# Level_Detector.net
KiCad netlist of a schematic drawn in Altium Designer
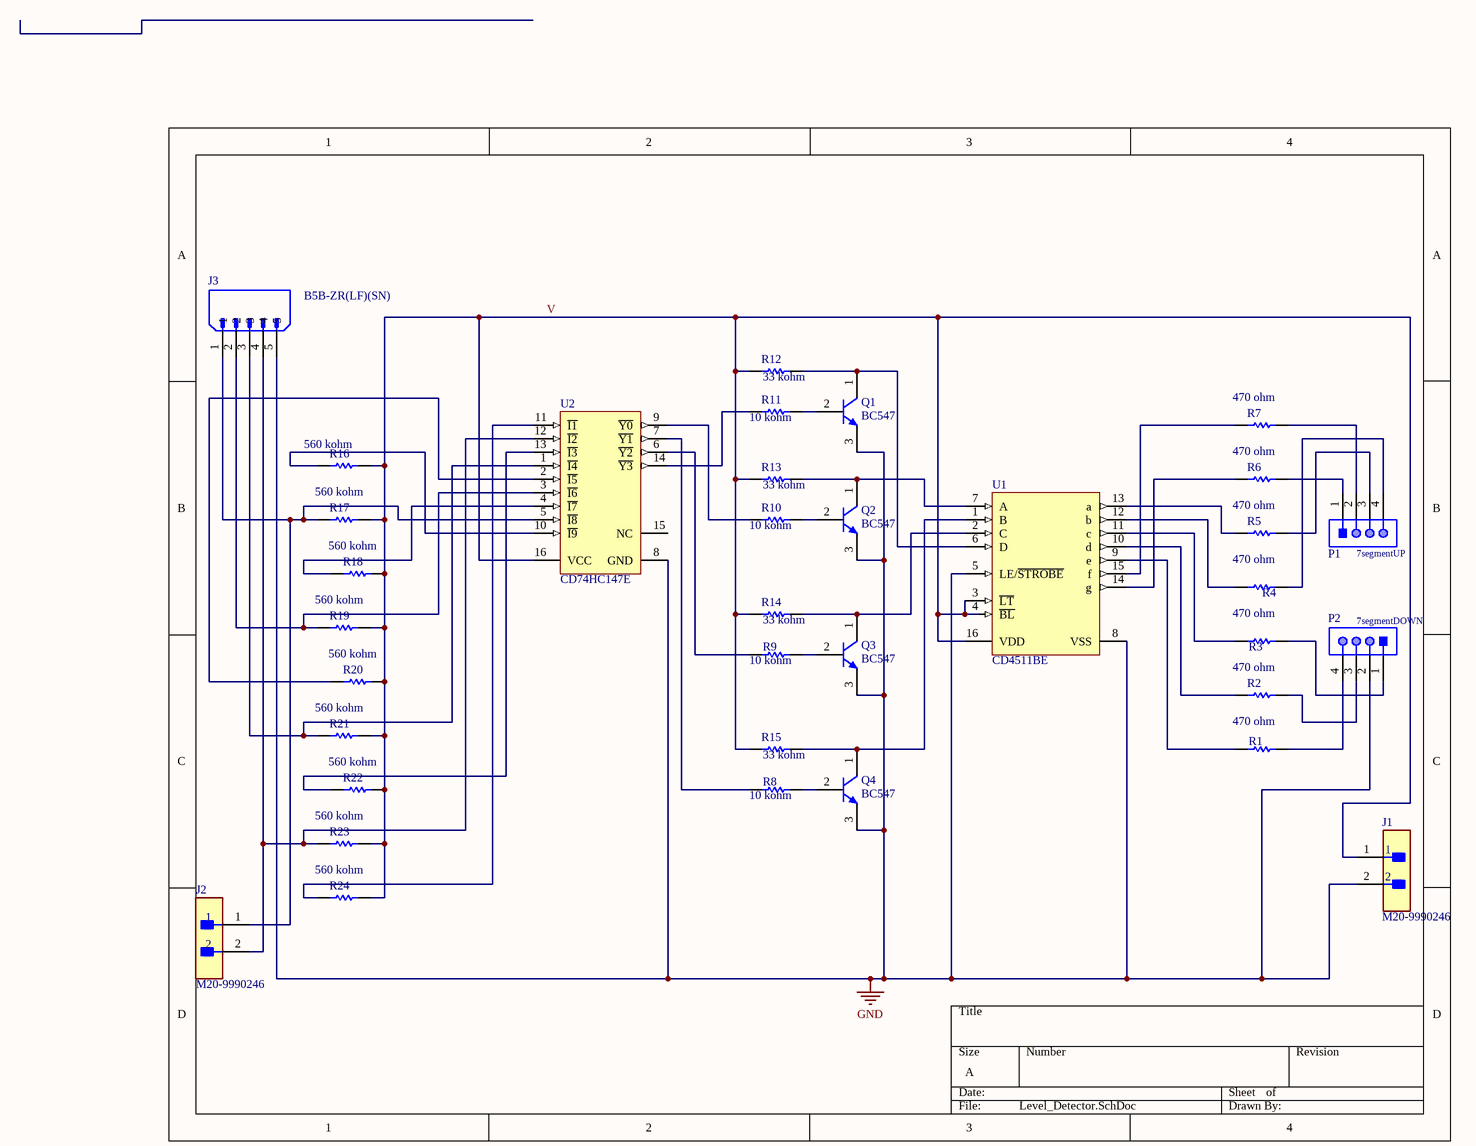
[diagram p0: Level_Detector.SchDoc]

(export (version "E")
  (design (tool "Eeschema 10.0.6"))
  (components
    (comp (ref "J1")
      (value "M20-9990246")
      (footprint "FP-M20-9990246-MFG")
      (description "CONN HEADER VERT 2POS 2.54MM")
      (fields
        (field (name "OCTOPART") "https://octopart.com/m20-9990246-harwin-2590635")
        (field (name "MANUFACTURER") "Harwin")
      )
      (libsource (lib "Altium Content Vault") (part "3bc925449376181038e59eaffc5286c"))
    )
    (comp (ref "J2")
      (value "M20-9990246")
      (footprint "FP-M20-9990246-MFG")
      (description "CONN HEADER VERT 2POS 2.54MM")
      (fields
        (field (name "OCTOPART") "https://octopart.com/m20-9990246-harwin-2590635")
        (field (name "MANUFACTURER") "Harwin")
      )
      (libsource (lib "") (part "3bc925449376181038e59eaffc5286c_1"))
    )
    (comp (ref "J3")
      (value "B5B-ZR(LF)(SN)")
      (footprint "JST_B5B-ZR(LF)(SN):JST_B5B-ZR(LF)(SN)")
      (description "Connector Header Through Hole 5 position 0.059 (1.50mm)")
      (fields (field (name "MF") "JST Sales"))
      (libsource (lib "B5B-ZR(LF)(SN)") (part "B5B-ZR(LF)(SN)"))
    )
    (comp (ref "P1")
      (value "7segmentUP")
      (footprint "61900411121")
      (description "Male Locking Header WR-WTB, THT, Vertical, pitch 2.54 mm, 1 x 4 position")
      (fields
        (field (name "MANUFACTURER") "Wurth Elektronik")
        (field (name "PART NUMBER") "61900411121")
        (field (name "PUBLISHER") "WurthElektronik")
      )
      (libsource (lib "") (part "WE-CN-1P-M-R4_1"))
    )
    (comp (ref "P2")
      (value "7segmentDOWN")
      (footprint "61900411121")
      (description "Male Locking Header WR-WTB, THT, Vertical, pitch 2.54 mm, 1 x 4 position")
      (fields
        (field (name "MANUFACTURER") "Wurth Elektronik")
        (field (name "PART NUMBER") "61900411121")
        (field (name "PUBLISHER") "WurthElektronik")
      )
      (libsource (lib "Altium Content Vault") (part "WE-CN-1P-M-R4"))
    )
    (comp (ref "Q1")
      (value "BC547")
      (footprint "ONSC-TO-92-3-29-11_AM_BL")
      (description "Amplifier Transistor, NPN Silicon, 3-Pin TO-92, Pb-Free, Tape and Reel")
      (fields (field (name "MANUFACTURER") "On Semiconductor") (field (name "PARTNUMBER") "BC547BRL1G"))
      (libsource (lib "Altium Content Vault") (part "ONSC-NPN-C1B2E3-3"))
    )
    (comp (ref "Q2")
      (value "BC547")
      (footprint "ONSC-TO-92-3-29-11_AM_BL")
      (description "Amplifier Transistor, NPN Silicon, 3-Pin TO-92, Pb-Free, Tape and Reel")
      (fields (field (name "MANUFACTURER") "On Semiconductor") (field (name "PARTNUMBER") "BC547BRL1G"))
      (libsource (lib "Altium Content Vault") (part "ONSC-NPN-C1B2E3-3"))
    )
    (comp (ref "Q3")
      (value "BC547")
      (footprint "ONSC-TO-92-3-29-11_AM_BL")
      (description "Amplifier Transistor, NPN Silicon, 3-Pin TO-92, Pb-Free, Tape and Reel")
      (fields (field (name "MANUFACTURER") "On Semiconductor") (field (name "PARTNUMBER") "BC547BRL1G"))
      (libsource (lib "Altium Content Vault") (part "ONSC-NPN-C1B2E3-3"))
    )
    (comp (ref "Q4")
      (value "BC547")
      (footprint "ONSC-TO-92-3-29-11_AM_BL")
      (description "Amplifier Transistor, NPN Silicon, 3-Pin TO-92, Pb-Free, Tape and Reel")
      (fields (field (name "MANUFACTURER") "On Semiconductor") (field (name "PARTNUMBER") "BC547BRL1G"))
      (libsource (lib "Altium Content Vault") (part "ONSC-NPN-C1B2E3-3"))
    )
    (comp (ref "R1")
      (value "MFR-25FBF52-1K")
      (footprint "RESA60-630X240")
      (description "Axial Resistor, 1 KOhm, +/- 1%, 250 mW, -55 to 155 degC, 2-Pin THD, RoHS, Bulk")
      (fields (field (name "TOLERANCE") "1%") (field (name "RESISTANCE") "470 ohm"))
      (libsource (lib "Altium Content Vault") (part "RES-2"))
    )
    (comp (ref "R2")
      (value "MFR-25FBF52-1K")
      (footprint "RESA60-630X240")
      (description "Axial Resistor, 1 KOhm, +/- 1%, 250 mW, -55 to 155 degC, 2-Pin THD, RoHS, Bulk")
      (fields (field (name "TOLERANCE") "1%") (field (name "RESISTANCE") "470 ohm"))
      (libsource (lib "Altium Content Vault") (part "RES-2"))
    )
    (comp (ref "R3")
      (value "MFR-25FBF52-1K")
      (footprint "RESA60-630X240")
      (description "Axial Resistor, 1 KOhm, +/- 1%, 250 mW, -55 to 155 degC, 2-Pin THD, RoHS, Bulk")
      (fields (field (name "TOLERANCE") "1%") (field (name "RESISTANCE") "470 ohm"))
      (libsource (lib "Altium Content Vault") (part "RES-2"))
    )
    (comp (ref "R4")
      (value "MFR-25FBF52-1K")
      (footprint "RESA60-630X240")
      (description "Axial Resistor, 1 KOhm, +/- 1%, 250 mW, -55 to 155 degC, 2-Pin THD, RoHS, Bulk")
      (fields (field (name "TOLERANCE") "1%") (field (name "RESISTANCE") "470 ohm"))
      (libsource (lib "Altium Content Vault") (part "RES-2"))
    )
    (comp (ref "R5")
      (value "MFR-25FBF52-1K")
      (footprint "RESA60-630X240")
      (description "Axial Resistor, 1 KOhm, +/- 1%, 250 mW, -55 to 155 degC, 2-Pin THD, RoHS, Bulk")
      (fields (field (name "TOLERANCE") "1%") (field (name "RESISTANCE") "470 ohm"))
      (libsource (lib "Altium Content Vault") (part "RES-2"))
    )
    (comp (ref "R6")
      (value "MFR-25FBF52-1K")
      (footprint "RESA60-630X240")
      (description "Axial Resistor, 1 KOhm, +/- 1%, 250 mW, -55 to 155 degC, 2-Pin THD, RoHS, Bulk")
      (fields (field (name "TOLERANCE") "1%") (field (name "RESISTANCE") "470 ohm"))
      (libsource (lib "Altium Content Vault") (part "RES-2"))
    )
    (comp (ref "R7")
      (value "MFR-25FBF52-1K")
      (footprint "RESA60-630X240")
      (description "Axial Resistor, 1 KOhm, +/- 1%, 250 mW, -55 to 155 degC, 2-Pin THD, RoHS, Bulk")
      (fields (field (name "TOLERANCE") "1%") (field (name "RESISTANCE") "470 ohm"))
      (libsource (lib "Altium Content Vault") (part "RES-2"))
    )
    (comp (ref "R8")
      (value "MFR-25FBF52-1K")
      (footprint "RESA60-630X240")
      (description "Axial Resistor, 1 KOhm, +/- 1%, 250 mW, -55 to 155 degC, 2-Pin THD, RoHS, Bulk")
      (fields (field (name "TOLERANCE") "1%") (field (name "RESISTANCE") "10 kohm"))
      (libsource (lib "Altium Content Vault") (part "RES-2"))
    )
    (comp (ref "R9")
      (value "MFR-25FBF52-1K")
      (footprint "RESA60-630X240")
      (description "Axial Resistor, 1 KOhm, +/- 1%, 250 mW, -55 to 155 degC, 2-Pin THD, RoHS, Bulk")
      (fields (field (name "TOLERANCE") "1%") (field (name "RESISTANCE") "10 kohm"))
      (libsource (lib "Altium Content Vault") (part "RES-2"))
    )
    (comp (ref "R10")
      (value "MFR-25FBF52-1K")
      (footprint "RESA60-630X240")
      (description "Axial Resistor, 1 KOhm, +/- 1%, 250 mW, -55 to 155 degC, 2-Pin THD, RoHS, Bulk")
      (fields (field (name "TOLERANCE") "1%") (field (name "RESISTANCE") "10 kohm"))
      (libsource (lib "Altium Content Vault") (part "RES-2"))
    )
    (comp (ref "R11")
      (value "MFR-25FBF52-1K")
      (footprint "RESA60-630X240")
      (description "Axial Resistor, 1 KOhm, +/- 1%, 250 mW, -55 to 155 degC, 2-Pin THD, RoHS, Bulk")
      (fields (field (name "TOLERANCE") "1%") (field (name "RESISTANCE") "10 kohm"))
      (libsource (lib "Altium Content Vault") (part "RES-2"))
    )
    (comp (ref "R12")
      (value "MFR-25FBF52-1K")
      (footprint "RESA60-630X240")
      (description "Axial Resistor, 1 KOhm, +/- 1%, 250 mW, -55 to 155 degC, 2-Pin THD, RoHS, Bulk")
      (fields (field (name "TOLERANCE") "1%") (field (name "RESISTANCE") "33 kohm"))
      (libsource (lib "Altium Content Vault") (part "RES-2"))
    )
    (comp (ref "R13")
      (value "MFR-25FBF52-1K")
      (footprint "RESA60-630X240")
      (description "Axial Resistor, 1 KOhm, +/- 1%, 250 mW, -55 to 155 degC, 2-Pin THD, RoHS, Bulk")
      (fields (field (name "TOLERANCE") "1%") (field (name "RESISTANCE") "33 kohm"))
      (libsource (lib "Altium Content Vault") (part "RES-2"))
    )
    (comp (ref "R14")
      (value "MFR-25FBF52-1K")
      (footprint "RESA60-630X240")
      (description "Axial Resistor, 1 KOhm, +/- 1%, 250 mW, -55 to 155 degC, 2-Pin THD, RoHS, Bulk")
      (fields (field (name "TOLERANCE") "1%") (field (name "RESISTANCE") "33 kohm"))
      (libsource (lib "Altium Content Vault") (part "RES-2"))
    )
    (comp (ref "R15")
      (value "MFR-25FBF52-1K")
      (footprint "RESA60-630X240")
      (description "Axial Resistor, 1 KOhm, +/- 1%, 250 mW, -55 to 155 degC, 2-Pin THD, RoHS, Bulk")
      (fields (field (name "TOLERANCE") "1%") (field (name "RESISTANCE") "33 kohm"))
      (libsource (lib "Altium Content Vault") (part "RES-2"))
    )
    (comp (ref "R16")
      (value "MFR-25FBF52-1K")
      (footprint "RESA60-630X240")
      (description "Axial Resistor, 1 KOhm, +/- 1%, 250 mW, -55 to 155 degC, 2-Pin THD, RoHS, Bulk")
      (fields (field (name "TOLERANCE") "1%") (field (name "RESISTANCE") "560 kohm"))
      (libsource (lib "Altium Content Vault") (part "RES-2"))
    )
    (comp (ref "R17")
      (value "MFR-25FBF52-1K")
      (footprint "RESA60-630X240")
      (description "Axial Resistor, 1 KOhm, +/- 1%, 250 mW, -55 to 155 degC, 2-Pin THD, RoHS, Bulk")
      (fields (field (name "TOLERANCE") "1%") (field (name "RESISTANCE") "560 kohm"))
      (libsource (lib "Altium Content Vault") (part "RES-2"))
    )
    (comp (ref "R18")
      (value "MFR-25FBF52-1K")
      (footprint "RESA60-630X240")
      (description "Axial Resistor, 1 KOhm, +/- 1%, 250 mW, -55 to 155 degC, 2-Pin THD, RoHS, Bulk")
      (fields (field (name "TOLERANCE") "1%") (field (name "RESISTANCE") "560 kohm"))
      (libsource (lib "Altium Content Vault") (part "RES-2"))
    )
    (comp (ref "R19")
      (value "MFR-25FBF52-1K")
      (footprint "RESA60-630X240")
      (description "Axial Resistor, 1 KOhm, +/- 1%, 250 mW, -55 to 155 degC, 2-Pin THD, RoHS, Bulk")
      (fields (field (name "TOLERANCE") "1%") (field (name "RESISTANCE") "560 kohm"))
      (libsource (lib "Altium Content Vault") (part "RES-2"))
    )
    (comp (ref "R20")
      (value "MFR-25FBF52-1K")
      (footprint "RESA60-630X240")
      (description "Axial Resistor, 1 KOhm, +/- 1%, 250 mW, -55 to 155 degC, 2-Pin THD, RoHS, Bulk")
      (fields (field (name "TOLERANCE") "1%") (field (name "RESISTANCE") "560 kohm"))
      (libsource (lib "Altium Content Vault") (part "RES-2"))
    )
    (comp (ref "R21")
      (value "MFR-25FBF52-1K")
      (footprint "RESA60-630X240")
      (description "Axial Resistor, 1 KOhm, +/- 1%, 250 mW, -55 to 155 degC, 2-Pin THD, RoHS, Bulk")
      (fields (field (name "TOLERANCE") "1%") (field (name "RESISTANCE") "560 kohm"))
      (libsource (lib "Altium Content Vault") (part "RES-2"))
    )
    (comp (ref "R22")
      (value "MFR-25FBF52-1K")
      (footprint "RESA60-630X240")
      (description "Axial Resistor, 1 KOhm, +/- 1%, 250 mW, -55 to 155 degC, 2-Pin THD, RoHS, Bulk")
      (fields (field (name "TOLERANCE") "1%") (field (name "RESISTANCE") "560 kohm"))
      (libsource (lib "Altium Content Vault") (part "RES-2"))
    )
    (comp (ref "R23")
      (value "MFR-25FBF52-1K")
      (footprint "RESA60-630X240")
      (description "Axial Resistor, 1 KOhm, +/- 1%, 250 mW, -55 to 155 degC, 2-Pin THD, RoHS, Bulk")
      (fields (field (name "TOLERANCE") "1%") (field (name "RESISTANCE") "560 kohm"))
      (libsource (lib "Altium Content Vault") (part "RES-2"))
    )
    (comp (ref "R24")
      (value "MFR-25FBF52-1K")
      (footprint "RESA60-630X240")
      (description "Axial Resistor, 1 KOhm, +/- 1%, 250 mW, -55 to 155 degC, 2-Pin THD, RoHS, Bulk")
      (fields (field (name "TOLERANCE") "1%") (field (name "RESISTANCE") "560 kohm"))
      (libsource (lib "Altium Content Vault") (part "RES-2"))
    )
    (comp (ref "U1")
      (value "CD4511BE")
      (footprint "N0016A")
      (fields (field (name "MANUFACTURER") "Texas Instruments"))
      (libsource (lib "Altium Content Vault") (part "TI-CD4511BX16"))
    )
    (comp (ref "U2")
      (value "CD74HC147E")
      (footprint "N0016A")
      (description "High Speed CMOS Logic 10-to-4 Line Priority Encoder, N0016A, TUBE")
      (fields
        (field (name "GENERIC PART NUMBER") "CD74HC147")
        (field (name "MANUFACTURER") "Texas Instruments")
      )
      (libsource (lib "Altium Content Vault") (part "TI-CDX4HCX147-16"))
    )
  )
  (nets
    (net (code "1") (name "/V") (class "Default")
      (node (ref "J1") (pin "1") (pinfunction "1_1") (pintype "passive"))
      (node (ref "R12") (pin "1") (pinfunction "1_1") (pintype "passive"))
      (node (ref "R13") (pin "1") (pinfunction "1_1") (pintype "passive"))
      (node (ref "R14") (pin "1") (pinfunction "1_1") (pintype "passive"))
      (node (ref "R15") (pin "1") (pinfunction "1_1") (pintype "passive"))
      (node (ref "R16") (pin "2") (pinfunction "2_2") (pintype "passive"))
      (node (ref "R17") (pin "2") (pinfunction "2_2") (pintype "passive"))
      (node (ref "R18") (pin "2") (pinfunction "2_2") (pintype "passive"))
      (node (ref "R19") (pin "2") (pinfunction "2_2") (pintype "passive"))
      (node (ref "R20") (pin "2") (pinfunction "2_2") (pintype "passive"))
      (node (ref "R21") (pin "2") (pinfunction "2_2") (pintype "passive"))
      (node (ref "R22") (pin "2") (pinfunction "2_2") (pintype "passive"))
      (node (ref "R23") (pin "2") (pinfunction "2_2") (pintype "passive"))
      (node (ref "R24") (pin "2") (pinfunction "2_2") (pintype "passive"))
      (node (ref "U1") (pin "16") (pinfunction "VDD_16") (pintype "power_in"))
      (node (ref "U1") (pin "3") (pinfunction "~{LT}_3") (pintype "input"))
      (node (ref "U1") (pin "4") (pinfunction "~{BL}_4") (pintype "input"))
      (node (ref "U2") (pin "16") (pinfunction "VCC_16") (pintype "power_in"))
    )
    (net (code "2") (name "GND") (class "Default")
      (node (ref "J1") (pin "2") (pinfunction "2_2") (pintype "passive"))
      (node (ref "J3") (pin "5") (pinfunction "5_5") (pintype "passive"))
      (node (ref "P2") (pin "2") (pinfunction "2_2") (pintype "passive"))
      (node (ref "Q1") (pin "3") (pinfunction "E_3") (pintype "passive"))
      (node (ref "Q2") (pin "3") (pinfunction "E_3") (pintype "passive"))
      (node (ref "Q3") (pin "3") (pinfunction "E_3") (pintype "passive"))
      (node (ref "Q4") (pin "3") (pinfunction "E_3") (pintype "passive"))
      (node (ref "U1") (pin "5") (pinfunction "LE/~{STROBE}_5") (pintype "input"))
      (node (ref "U1") (pin "8") (pinfunction "VSS_8") (pintype "power_in"))
      (node (ref "U2") (pin "8") (pinfunction "GND_8") (pintype "power_in"))
    )
    (net (code "3") (name "Net-(P1-Pad1)") (class "Default")
      (node (ref "P1") (pin "1") (pinfunction "1_1") (pintype "passive"))
      (node (ref "R6") (pin "2") (pinfunction "2_2") (pintype "passive"))
    )
    (net (code "4") (name "Net-(P1-Pad2)") (class "Default")
      (node (ref "P1") (pin "2") (pinfunction "2_2") (pintype "passive"))
      (node (ref "R7") (pin "2") (pinfunction "2_2") (pintype "passive"))
    )
    (net (code "5") (name "Net-(P1-Pad3)") (class "Default")
      (node (ref "P1") (pin "3") (pinfunction "3_3") (pintype "passive"))
      (node (ref "R5") (pin "2") (pinfunction "2_2") (pintype "passive"))
    )
    (net (code "6") (name "Net-(P1-Pad4)") (class "Default")
      (node (ref "P1") (pin "4") (pinfunction "4_4") (pintype "passive"))
      (node (ref "R4") (pin "2") (pinfunction "2_2") (pintype "passive"))
    )
    (net (code "7") (name "Net-(P2-Pad1)") (class "Default")
      (node (ref "P2") (pin "1") (pinfunction "1_1") (pintype "passive"))
      (node (ref "R3") (pin "2") (pinfunction "2_2") (pintype "passive"))
    )
    (net (code "8") (name "Net-(P2-Pad3)") (class "Default")
      (node (ref "P2") (pin "3") (pinfunction "3_3") (pintype "passive"))
      (node (ref "R2") (pin "2") (pinfunction "2_2") (pintype "passive"))
    )
    (net (code "9") (name "Net-(P2-Pad4)") (class "Default")
      (node (ref "P2") (pin "4") (pinfunction "4_4") (pintype "passive"))
      (node (ref "R1") (pin "2") (pinfunction "2_2") (pintype "passive"))
    )
    (net (code "10") (name "Net-(Q1-B)") (class "Default")
      (node (ref "Q1") (pin "2") (pinfunction "B_2") (pintype "passive"))
      (node (ref "R11") (pin "2") (pinfunction "2_2") (pintype "passive"))
    )
    (net (code "11") (name "Net-(Q1-C)") (class "Default")
      (node (ref "Q1") (pin "1") (pinfunction "C_1") (pintype "passive"))
      (node (ref "R12") (pin "2") (pinfunction "2_2") (pintype "passive"))
      (node (ref "U1") (pin "6") (pinfunction "D_6") (pintype "input"))
    )
    (net (code "12") (name "Net-(Q2-B)") (class "Default")
      (node (ref "Q2") (pin "2") (pinfunction "B_2") (pintype "passive"))
      (node (ref "R10") (pin "2") (pinfunction "2_2") (pintype "passive"))
    )
    (net (code "13") (name "Net-(Q2-C)") (class "Default")
      (node (ref "Q2") (pin "1") (pinfunction "C_1") (pintype "passive"))
      (node (ref "R13") (pin "2") (pinfunction "2_2") (pintype "passive"))
      (node (ref "U1") (pin "7") (pinfunction "A_7") (pintype "input"))
    )
    (net (code "14") (name "Net-(Q3-B)") (class "Default")
      (node (ref "Q3") (pin "2") (pinfunction "B_2") (pintype "passive"))
      (node (ref "R9") (pin "2") (pinfunction "2_2") (pintype "passive"))
    )
    (net (code "15") (name "Net-(Q3-C)") (class "Default")
      (node (ref "Q3") (pin "1") (pinfunction "C_1") (pintype "passive"))
      (node (ref "R14") (pin "2") (pinfunction "2_2") (pintype "passive"))
      (node (ref "U1") (pin "2") (pinfunction "C_2") (pintype "input"))
    )
    (net (code "16") (name "Net-(Q4-B)") (class "Default")
      (node (ref "Q4") (pin "2") (pinfunction "B_2") (pintype "passive"))
      (node (ref "R8") (pin "2") (pinfunction "2_2") (pintype "passive"))
    )
    (net (code "17") (name "Net-(Q4-C)") (class "Default")
      (node (ref "Q4") (pin "1") (pinfunction "C_1") (pintype "passive"))
      (node (ref "R15") (pin "2") (pinfunction "2_2") (pintype "passive"))
      (node (ref "U1") (pin "1") (pinfunction "B_1") (pintype "input"))
    )
    (net (code "18") (name "Net-(U1-a)") (class "Default")
      (node (ref "R5") (pin "1") (pinfunction "1_1") (pintype "passive"))
      (node (ref "U1") (pin "13") (pinfunction "a_13") (pintype "output"))
    )
    (net (code "19") (name "Net-(U1-b)") (class "Default")
      (node (ref "R4") (pin "1") (pinfunction "1_1") (pintype "passive"))
      (node (ref "U1") (pin "12") (pinfunction "b_12") (pintype "output"))
    )
    (net (code "20") (name "Net-(U1-c)") (class "Default")
      (node (ref "R3") (pin "1") (pinfunction "1_1") (pintype "passive"))
      (node (ref "U1") (pin "11") (pinfunction "c_11") (pintype "output"))
    )
    (net (code "21") (name "Net-(U1-d)") (class "Default")
      (node (ref "R2") (pin "1") (pinfunction "1_1") (pintype "passive"))
      (node (ref "U1") (pin "10") (pinfunction "d_10") (pintype "output"))
    )
    (net (code "22") (name "Net-(U1-e)") (class "Default")
      (node (ref "R1") (pin "1") (pinfunction "1_1") (pintype "passive"))
      (node (ref "U1") (pin "9") (pinfunction "e_9") (pintype "output"))
    )
    (net (code "23") (name "Net-(U1-f)") (class "Default")
      (node (ref "R7") (pin "1") (pinfunction "1_1") (pintype "passive"))
      (node (ref "U1") (pin "15") (pinfunction "f_15") (pintype "output"))
    )
    (net (code "24") (name "Net-(U1-g)") (class "Default")
      (node (ref "R6") (pin "1") (pinfunction "1_1") (pintype "passive"))
      (node (ref "U1") (pin "14") (pinfunction "g_14") (pintype "output"))
    )
    (net (code "25") (name "Net-(U2-~{I1})") (class "Default")
      (node (ref "R24") (pin "1") (pinfunction "1_1") (pintype "passive"))
      (node (ref "U2") (pin "11") (pinfunction "~{I1}_11") (pintype "input"))
    )
    (net (code "26") (name "Net-(U2-~{I2})") (class "Default")
      (node (ref "J2") (pin "2") (pinfunction "2_2") (pintype "passive"))
      (node (ref "J3") (pin "4") (pinfunction "4_4") (pintype "passive"))
      (node (ref "R23") (pin "1") (pinfunction "1_1") (pintype "passive"))
      (node (ref "U2") (pin "12") (pinfunction "~{I2}_12") (pintype "input"))
    )
    (net (code "27") (name "Net-(U2-~{I3})") (class "Default")
      (node (ref "R22") (pin "1") (pinfunction "1_1") (pintype "passive"))
      (node (ref "U2") (pin "13") (pinfunction "~{I3}_13") (pintype "input"))
    )
    (net (code "28") (name "Net-(U2-~{I4})") (class "Default")
      (node (ref "J3") (pin "3") (pinfunction "3_3") (pintype "passive"))
      (node (ref "R21") (pin "1") (pinfunction "1_1") (pintype "passive"))
      (node (ref "U2") (pin "1") (pinfunction "~{I4}_1") (pintype "input"))
    )
    (net (code "29") (name "Net-(U2-~{I5})") (class "Default")
      (node (ref "R20") (pin "1") (pinfunction "1_1") (pintype "passive"))
      (node (ref "U2") (pin "2") (pinfunction "~{I5}_2") (pintype "input"))
    )
    (net (code "30") (name "Net-(U2-~{I6})") (class "Default")
      (node (ref "J3") (pin "2") (pinfunction "2_2") (pintype "passive"))
      (node (ref "R19") (pin "1") (pinfunction "1_1") (pintype "passive"))
      (node (ref "U2") (pin "3") (pinfunction "~{I6}_3") (pintype "input"))
    )
    (net (code "31") (name "Net-(U2-~{I7})") (class "Default")
      (node (ref "R18") (pin "1") (pinfunction "1_1") (pintype "passive"))
      (node (ref "U2") (pin "4") (pinfunction "~{I7}_4") (pintype "input"))
    )
    (net (code "32") (name "Net-(U2-~{I8})") (class "Default")
      (node (ref "J2") (pin "1") (pinfunction "1_1") (pintype "passive"))
      (node (ref "J3") (pin "1") (pinfunction "1_1") (pintype "passive"))
      (node (ref "R17") (pin "1") (pinfunction "1_1") (pintype "passive"))
      (node (ref "U2") (pin "5") (pinfunction "~{I8}_5") (pintype "input"))
    )
    (net (code "33") (name "Net-(U2-~{I9})") (class "Default")
      (node (ref "R16") (pin "1") (pinfunction "1_1") (pintype "passive"))
      (node (ref "U2") (pin "10") (pinfunction "~{I9}_10") (pintype "input"))
    )
    (net (code "34") (name "Net-(U2-~{Y0})") (class "Default")
      (node (ref "R10") (pin "1") (pinfunction "1_1") (pintype "passive"))
      (node (ref "U2") (pin "9") (pinfunction "~{Y0}_9") (pintype "output"))
    )
    (net (code "35") (name "Net-(U2-~{Y1})") (class "Default")
      (node (ref "R8") (pin "1") (pinfunction "1_1") (pintype "passive"))
      (node (ref "U2") (pin "7") (pinfunction "~{Y1}_7") (pintype "output"))
    )
    (net (code "36") (name "Net-(U2-~{Y2})") (class "Default")
      (node (ref "R9") (pin "1") (pinfunction "1_1") (pintype "passive"))
      (node (ref "U2") (pin "6") (pinfunction "~{Y2}_6") (pintype "output"))
    )
    (net (code "37") (name "Net-(U2-~{Y3})") (class "Default")
      (node (ref "R11") (pin "1") (pinfunction "1_1") (pintype "passive"))
      (node (ref "U2") (pin "14") (pinfunction "~{Y3}_14") (pintype "output"))
    )
    (net (code "38") (name "unconnected-(U2-NC-Pad15)") (class "Default")
      (node (ref "U2") (pin "15") (pinfunction "NC_15") (pintype "passive"))
    )
  )
)
